# ARIKPO.net
KiCad netlist of a schematic drawn in Altium Designer
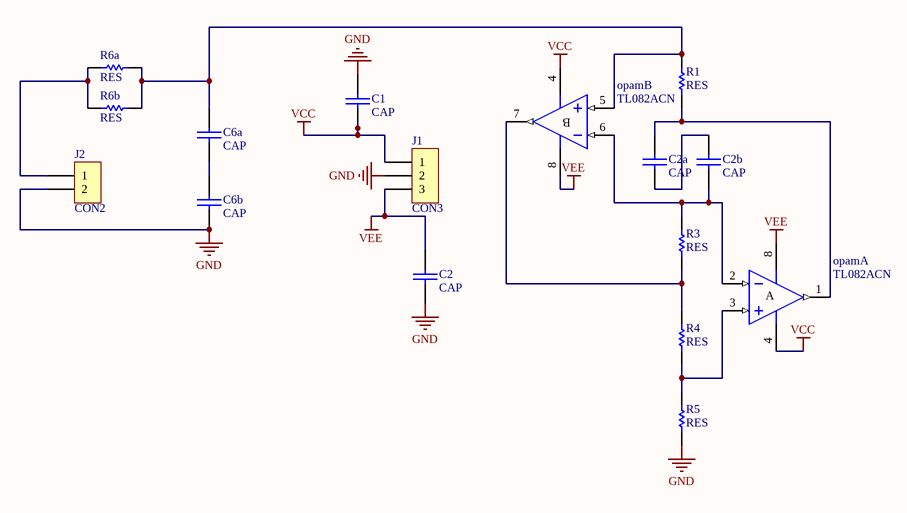
[diagram p0: ARIKPO.SchDoc]

(export (version "E")
  (design (tool "Eeschema 10.0.6"))
  (components
    (comp (ref "C1") (value "CAP") (footprint "CAP200") (libsource (lib "LIBEBAL") (part "CAP")))
    (comp (ref "C2") (value "CAP") (footprint "CAP200") (libsource (lib "LIBEBAL") (part "CAP")))
    (comp (ref "C2a") (value "CAP") (footprint "CAP200") (libsource (lib "LIBEBAL") (part "CAP")))
    (comp (ref "C2b") (value "CAP") (footprint "CAP200") (libsource (lib "LIBEBAL") (part "CAP")))
    (comp (ref "C6a") (value "CAP") (footprint "CAP200") (libsource (lib "LIBEBAL") (part "CAP")))
    (comp (ref "C6b") (value "CAP") (footprint "CAP200") (libsource (lib "LIBEBAL") (part "CAP")))
    (comp (ref "J1") (value "CON3") (footprint "SIP3") (libsource (lib "LIBEBAL") (part "CON3")))
    (comp (ref "J2") (value "CON2") (footprint "SIP2") (libsource (lib "LIBEBAL") (part "CON2")))
    (comp (ref "opam")
      (value "TL082ACN")
      (footprint "DIP8")
      (description "General-Purpose J-FET Dual Operational Amplifier")
      (fields (field (name "PUBLISHER") "Altium Limited"))
      (libsource (lib "ST Operational Amplifier") (part "TL082ACN"))
    )
    (comp (ref "R1") (value "RES") (footprint "RES300") (libsource (lib "LIBEBAL") (part "RES")))
    (comp (ref "R3") (value "RES") (footprint "RES300") (libsource (lib "LIBEBAL") (part "RES")))
    (comp (ref "R4") (value "RES") (footprint "RES300") (libsource (lib "LIBEBAL") (part "RES")))
    (comp (ref "R5") (value "RES") (footprint "RES300") (libsource (lib "LIBEBAL") (part "RES")))
    (comp (ref "R6a") (value "RES") (footprint "RES300") (libsource (lib "LIBEBAL") (part "RES")))
    (comp (ref "R6b") (value "RES") (footprint "RES300") (libsource (lib "LIBEBAL") (part "RES")))
  )
  (nets
    (net (code "1") (name "GND") (class "Default")
      (node (ref "C1") (pin "1") (pinfunction "1_1") (pintype "passive"))
      (node (ref "C2") (pin "2") (pinfunction "2_2") (pintype "passive"))
      (node (ref "C6b") (pin "2") (pinfunction "2_2") (pintype "passive"))
      (node (ref "J1") (pin "2") (pinfunction "2_2") (pintype "passive"))
      (node (ref "J2") (pin "2") (pinfunction "2_2") (pintype "passive"))
      (node (ref "R5") (pin "1") (pinfunction "1_1") (pintype "passive"))
    )
    (net (code "2") (name "Net-(C2a-Pad2)") (class "Default")
      (node (ref "C2a") (pin "2") (pinfunction "2_2") (pintype "passive"))
      (node (ref "C2b") (pin "1") (pinfunction "1_1") (pintype "passive"))
    )
    (net (code "3") (name "Net-(C6a-Pad2)") (class "Default")
      (node (ref "C6a") (pin "2") (pinfunction "2_2") (pintype "passive"))
      (node (ref "C6b") (pin "1") (pinfunction "1_1") (pintype "passive"))
    )
    (net (code "4") (name "Net-(J2-Pad1)") (class "Default")
      (node (ref "J2") (pin "1") (pinfunction "1_1") (pintype "passive"))
      (node (ref "R6a") (pin "1") (pinfunction "1_1") (pintype "passive"))
      (node (ref "R6b") (pin "1") (pinfunction "1_1") (pintype "passive"))
    )
    (net (code "5") (name "Net-(opamA-IN+)") (class "Default")
      (node (ref "R4") (pin "1") (pinfunction "1_1") (pintype "passive"))
      (node (ref "R5") (pin "2") (pinfunction "2_2") (pintype "passive"))
      (node (ref "opam") (pin "3") (pinfunction "IN+_3") (pintype "input"))
    )
    (net (code "6") (name "Net-(opamA-IN-)") (class "Default")
      (node (ref "C2b") (pin "2") (pinfunction "2_2") (pintype "passive"))
      (node (ref "R3") (pin "2") (pinfunction "2_2") (pintype "passive"))
      (node (ref "opam") (pin "2") (pinfunction "IN-_2") (pintype "input"))
      (node (ref "opam") (pin "6") (pinfunction "IN-_6") (pintype "input"))
    )
    (net (code "7") (name "Net-(opamA-OUT)") (class "Default")
      (node (ref "C2a") (pin "1") (pinfunction "1_1") (pintype "passive"))
      (node (ref "R1") (pin "1") (pinfunction "1_1") (pintype "passive"))
      (node (ref "opam") (pin "1") (pinfunction "OUT_1") (pintype "output"))
    )
    (net (code "8") (name "Net-(opamB-IN+)") (class "Default")
      (node (ref "C6a") (pin "1") (pinfunction "1_1") (pintype "passive"))
      (node (ref "R1") (pin "2") (pinfunction "2_2") (pintype "passive"))
      (node (ref "R6a") (pin "2") (pinfunction "2_2") (pintype "passive"))
      (node (ref "R6b") (pin "2") (pinfunction "2_2") (pintype "passive"))
      (node (ref "opam") (pin "5") (pinfunction "IN+_5") (pintype "input"))
    )
    (net (code "9") (name "Net-(opamB-OUT)") (class "Default")
      (node (ref "R3") (pin "1") (pinfunction "1_1") (pintype "passive"))
      (node (ref "R4") (pin "2") (pinfunction "2_2") (pintype "passive"))
      (node (ref "opam") (pin "7") (pinfunction "OUT_7") (pintype "output"))
    )
    (net (code "10") (name "VCC") (class "Default")
      (node (ref "C1") (pin "2") (pinfunction "2_2") (pintype "passive"))
      (node (ref "J1") (pin "1") (pinfunction "1_1") (pintype "passive"))
      (node (ref "opam") (pin "4") (pinfunction "V-_4") (pintype "power_in"))
    )
    (net (code "11") (name "VEE") (class "Default")
      (node (ref "C2") (pin "1") (pinfunction "1_1") (pintype "passive"))
      (node (ref "J1") (pin "3") (pinfunction "3_3") (pintype "passive"))
      (node (ref "opam") (pin "8") (pinfunction "V+_8") (pintype "power_in"))
    )
  )
)
